# stepperdriver.net
KiCad netlist of a schematic drawn in EAGLE
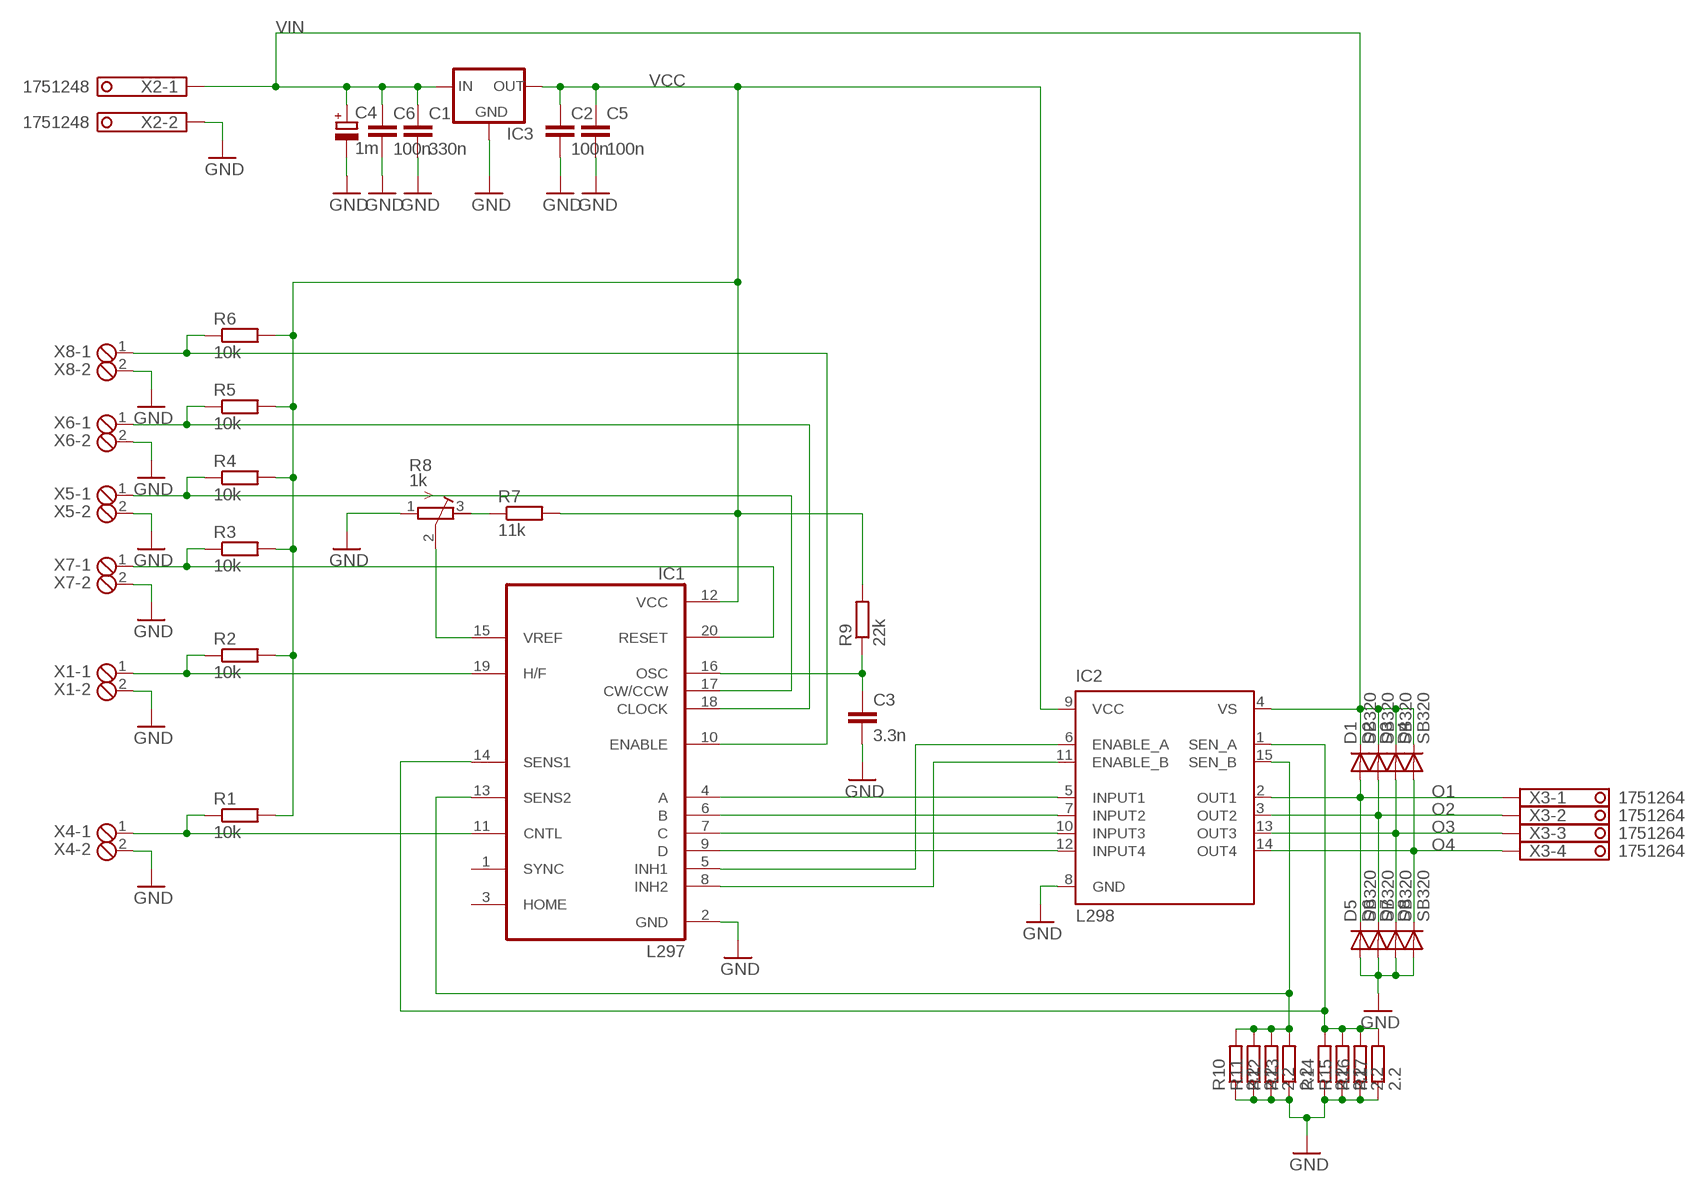
[diagram p0: schematic, sheet 1]

(export (version "E")
  (design (tool "Eeschema 10.0.6"))
  (components
    (comp (ref "C1")
      (value "330n")
      (footprint "eagle-import:C050-035X075")
      (libsource (lib "eagle-import") (part "C-EU050-035X075"))
    )
    (comp (ref "C2")
      (value "100n")
      (footprint "eagle-import:C050-035X075")
      (libsource (lib "eagle-import") (part "C-EU050-035X075"))
    )
    (comp (ref "C3")
      (value "3.3n")
      (footprint "eagle-import:C050-035X075")
      (libsource (lib "eagle-import") (part "C-EU050-035X075"))
    )
    (comp (ref "C4")
      (value "1m")
      (footprint "eagle-import:E5-13")
      (libsource (lib "eagle-import") (part "CPOL-EUE5-13"))
    )
    (comp (ref "C5")
      (value "100n")
      (footprint "eagle-import:C050-035X075")
      (libsource (lib "eagle-import") (part "C-EU050-035X075"))
    )
    (comp (ref "C6")
      (value "100n")
      (footprint "eagle-import:C050-035X075")
      (libsource (lib "eagle-import") (part "C-EU050-035X075"))
    )
    (comp (ref "D1")
      (value "SB320")
      (footprint "eagle-import:DO201-15")
      (libsource (lib "eagle-import") (part "SB320"))
    )
    (comp (ref "D2")
      (value "SB320")
      (footprint "eagle-import:DO201-15")
      (libsource (lib "eagle-import") (part "SB320"))
    )
    (comp (ref "D3")
      (value "SB320")
      (footprint "eagle-import:DO201-15")
      (libsource (lib "eagle-import") (part "SB320"))
    )
    (comp (ref "D4")
      (value "SB320")
      (footprint "eagle-import:DO201-15")
      (libsource (lib "eagle-import") (part "SB320"))
    )
    (comp (ref "D5")
      (value "SB320")
      (footprint "eagle-import:DO201-15")
      (libsource (lib "eagle-import") (part "SB320"))
    )
    (comp (ref "D6")
      (value "SB320")
      (footprint "eagle-import:DO201-15")
      (libsource (lib "eagle-import") (part "SB320"))
    )
    (comp (ref "D7")
      (value "SB320")
      (footprint "eagle-import:DO201-15")
      (libsource (lib "eagle-import") (part "SB320"))
    )
    (comp (ref "D8")
      (value "SB320")
      (footprint "eagle-import:DO201-15")
      (libsource (lib "eagle-import") (part "SB320"))
    )
    (comp (ref "IC1")
      (value "L297")
      (footprint "eagle-import:DIL20")
      (fields (field (name "MPN") "L297/1"))
      (libsource (lib "eagle-import") (part "L297"))
    )
    (comp (ref "IC2")
      (value "L298")
      (footprint "eagle-import:MULTIWATT-15")
      (fields (field (name "MPN") "L298N"))
      (libsource (lib "eagle-import") (part "L298"))
    )
    (comp (ref "IC3")
      (value "78XXS")
      (footprint "eagle-import:78XXS")
      (libsource (lib "eagle-import") (part "78XXS"))
    )
    (comp (ref "R1")
      (value "10k")
      (footprint "eagle-import:0207_10")
      (libsource (lib "eagle-import") (part "R-EU_0207/10"))
    )
    (comp (ref "R2")
      (value "10k")
      (footprint "eagle-import:0207_10")
      (libsource (lib "eagle-import") (part "R-EU_0207/10"))
    )
    (comp (ref "R3")
      (value "10k")
      (footprint "eagle-import:0207_10")
      (libsource (lib "eagle-import") (part "R-EU_0207/10"))
    )
    (comp (ref "R4")
      (value "10k")
      (footprint "eagle-import:0207_10")
      (libsource (lib "eagle-import") (part "R-EU_0207/10"))
    )
    (comp (ref "R5")
      (value "10k")
      (footprint "eagle-import:0207_10")
      (libsource (lib "eagle-import") (part "R-EU_0207/10"))
    )
    (comp (ref "R6")
      (value "10k")
      (footprint "eagle-import:0207_10")
      (libsource (lib "eagle-import") (part "R-EU_0207/10"))
    )
    (comp (ref "R7")
      (value "11k")
      (footprint "eagle-import:0207_10")
      (libsource (lib "eagle-import") (part "R-EU_0207/10"))
    )
    (comp (ref "R8")
      (value "1k")
      (footprint "eagle-import:RTRIM64W")
      (libsource (lib "eagle-import") (part "R-TRIMM64W"))
    )
    (comp (ref "R9")
      (value "22k")
      (footprint "eagle-import:0207_10")
      (libsource (lib "eagle-import") (part "R-EU_0207/10"))
    )
    (comp (ref "R10")
      (value "2.2")
      (footprint "eagle-import:0411_15")
      (libsource (lib "eagle-import") (part "R-EU_0411/15"))
    )
    (comp (ref "R11")
      (value "2.2")
      (footprint "eagle-import:0411_15")
      (libsource (lib "eagle-import") (part "R-EU_0411/15"))
    )
    (comp (ref "R12")
      (value "2.2")
      (footprint "eagle-import:0411_15")
      (libsource (lib "eagle-import") (part "R-EU_0411/15"))
    )
    (comp (ref "R13")
      (value "2.2")
      (footprint "eagle-import:0411_15")
      (libsource (lib "eagle-import") (part "R-EU_0411/15"))
    )
    (comp (ref "R14")
      (value "2.2")
      (footprint "eagle-import:0411_15")
      (libsource (lib "eagle-import") (part "R-EU_0411/15"))
    )
    (comp (ref "R15")
      (value "2.2")
      (footprint "eagle-import:0411_15")
      (libsource (lib "eagle-import") (part "R-EU_0411/15"))
    )
    (comp (ref "R16")
      (value "2.2")
      (footprint "eagle-import:0411_15")
      (libsource (lib "eagle-import") (part "R-EU_0411/15"))
    )
    (comp (ref "R17")
      (value "2.2")
      (footprint "eagle-import:0411_15")
      (libsource (lib "eagle-import") (part "R-EU_0411/15"))
    )
    (comp (ref "X1")
      (value "MPT2")
      (footprint "eagle-import:2POL254")
      (libsource (lib "eagle-import") (part "MPT2"))
    )
    (comp (ref "X2")
      (value "1751248")
      (footprint "eagle-import:1751248")
      (libsource (lib "eagle-import") (part "1751248"))
    )
    (comp (ref "X3")
      (value "1751264")
      (footprint "eagle-import:1751264")
      (libsource (lib "eagle-import") (part "1751264"))
    )
    (comp (ref "X4")
      (value "MPT2")
      (footprint "eagle-import:2POL254")
      (libsource (lib "eagle-import") (part "MPT2"))
    )
    (comp (ref "X5")
      (value "MPT2")
      (footprint "eagle-import:2POL254")
      (libsource (lib "eagle-import") (part "MPT2"))
    )
    (comp (ref "X6")
      (value "MPT2")
      (footprint "eagle-import:2POL254")
      (libsource (lib "eagle-import") (part "MPT2"))
    )
    (comp (ref "X7")
      (value "MPT2")
      (footprint "eagle-import:2POL254")
      (libsource (lib "eagle-import") (part "MPT2"))
    )
    (comp (ref "X8")
      (value "MPT2")
      (footprint "eagle-import:2POL254")
      (libsource (lib "eagle-import") (part "MPT2"))
    )
  )
  (nets
    (net (code "1") (name "/O1") (class "Default")
      (node (ref "D1") (pin "A") (pinfunction "A_A") (pintype "passive"))
      (node (ref "D5") (pin "C") (pinfunction "C_C") (pintype "passive"))
      (node (ref "IC2") (pin "2") (pinfunction "OUT1_2") (pintype "output"))
      (node (ref "X3") (pin "1") (pinfunction "K_1") (pintype "passive"))
    )
    (net (code "2") (name "/O2") (class "Default")
      (node (ref "D2") (pin "A") (pinfunction "A_A") (pintype "passive"))
      (node (ref "D6") (pin "C") (pinfunction "C_C") (pintype "passive"))
      (node (ref "IC2") (pin "3") (pinfunction "OUT2_3") (pintype "output"))
      (node (ref "X3") (pin "2") (pinfunction "K_2") (pintype "passive"))
    )
    (net (code "3") (name "/O3") (class "Default")
      (node (ref "D3") (pin "A") (pinfunction "A_A") (pintype "passive"))
      (node (ref "D7") (pin "C") (pinfunction "C_C") (pintype "passive"))
      (node (ref "IC2") (pin "13") (pinfunction "OUT3_13") (pintype "output"))
      (node (ref "X3") (pin "3") (pinfunction "K_3") (pintype "passive"))
    )
    (net (code "4") (name "/O4") (class "Default")
      (node (ref "D4") (pin "A") (pinfunction "A_A") (pintype "passive"))
      (node (ref "D8") (pin "C") (pinfunction "C_C") (pintype "passive"))
      (node (ref "IC2") (pin "14") (pinfunction "OUT4_14") (pintype "output"))
      (node (ref "X3") (pin "4") (pinfunction "K_4") (pintype "passive"))
    )
    (net (code "5") (name "/VCC") (class "Default")
      (node (ref "C2") (pin "1") (pinfunction "1_1") (pintype "passive"))
      (node (ref "C5") (pin "1") (pinfunction "1_1") (pintype "passive"))
      (node (ref "IC1") (pin "12") (pinfunction "VCC_12") (pintype "power_in"))
      (node (ref "IC2") (pin "9") (pinfunction "VCC_9") (pintype "power_in"))
      (node (ref "IC3") (pin "OUT") (pinfunction "OUT_OUT") (pintype "passive"))
      (node (ref "R1") (pin "2") (pinfunction "2_2") (pintype "passive"))
      (node (ref "R2") (pin "2") (pinfunction "2_2") (pintype "passive"))
      (node (ref "R3") (pin "2") (pinfunction "2_2") (pintype "passive"))
      (node (ref "R4") (pin "2") (pinfunction "2_2") (pintype "passive"))
      (node (ref "R5") (pin "2") (pinfunction "2_2") (pintype "passive"))
      (node (ref "R6") (pin "2") (pinfunction "2_2") (pintype "passive"))
      (node (ref "R7") (pin "2") (pinfunction "2_2") (pintype "passive"))
      (node (ref "R9") (pin "2") (pinfunction "2_2") (pintype "passive"))
    )
    (net (code "6") (name "/VIN") (class "Default")
      (node (ref "C1") (pin "1") (pinfunction "1_1") (pintype "passive"))
      (node (ref "C4") (pin "+") (pinfunction "+_+") (pintype "passive"))
      (node (ref "C6") (pin "1") (pinfunction "1_1") (pintype "passive"))
      (node (ref "D1") (pin "C") (pinfunction "C_C") (pintype "passive"))
      (node (ref "D2") (pin "C") (pinfunction "C_C") (pintype "passive"))
      (node (ref "D3") (pin "C") (pinfunction "C_C") (pintype "passive"))
      (node (ref "D4") (pin "C") (pinfunction "C_C") (pintype "passive"))
      (node (ref "IC2") (pin "4") (pinfunction "VS_4") (pintype "power_in"))
      (node (ref "IC3") (pin "IN") (pinfunction "IN_IN") (pintype "input"))
      (node (ref "X2") (pin "1") (pinfunction "K_1") (pintype "passive"))
    )
    (net (code "7") (name "GND") (class "Default")
      (node (ref "C1") (pin "2") (pinfunction "2_2") (pintype "passive"))
      (node (ref "C2") (pin "2") (pinfunction "2_2") (pintype "passive"))
      (node (ref "C3") (pin "2") (pinfunction "2_2") (pintype "passive"))
      (node (ref "C4") (pin "-") (pinfunction "-_-") (pintype "passive"))
      (node (ref "C5") (pin "2") (pinfunction "2_2") (pintype "passive"))
      (node (ref "C6") (pin "2") (pinfunction "2_2") (pintype "passive"))
      (node (ref "D5") (pin "A") (pinfunction "A_A") (pintype "passive"))
      (node (ref "D6") (pin "A") (pinfunction "A_A") (pintype "passive"))
      (node (ref "D7") (pin "A") (pinfunction "A_A") (pintype "passive"))
      (node (ref "D8") (pin "A") (pinfunction "A_A") (pintype "passive"))
      (node (ref "IC1") (pin "2") (pinfunction "GND_2") (pintype "power_in"))
      (node (ref "IC2") (pin "8") (pinfunction "GND_8") (pintype "power_in"))
      (node (ref "IC3") (pin "GND") (pinfunction "GND_GND") (pintype "input"))
      (node (ref "R10") (pin "1") (pinfunction "1_1") (pintype "passive"))
      (node (ref "R11") (pin "1") (pinfunction "1_1") (pintype "passive"))
      (node (ref "R12") (pin "1") (pinfunction "1_1") (pintype "passive"))
      (node (ref "R13") (pin "1") (pinfunction "1_1") (pintype "passive"))
      (node (ref "R14") (pin "1") (pinfunction "1_1") (pintype "passive"))
      (node (ref "R15") (pin "1") (pinfunction "1_1") (pintype "passive"))
      (node (ref "R16") (pin "1") (pinfunction "1_1") (pintype "passive"))
      (node (ref "R17") (pin "1") (pinfunction "1_1") (pintype "passive"))
      (node (ref "R8") (pin "1") (pinfunction "E_1") (pintype "passive"))
      (node (ref "X1") (pin "2") (pinfunction "1_2") (pintype "passive"))
      (node (ref "X2") (pin "2") (pinfunction "K_2") (pintype "passive"))
      (node (ref "X4") (pin "2") (pinfunction "1_2") (pintype "passive"))
      (node (ref "X5") (pin "2") (pinfunction "1_2") (pintype "passive"))
      (node (ref "X6") (pin "2") (pinfunction "1_2") (pintype "passive"))
      (node (ref "X7") (pin "2") (pinfunction "1_2") (pintype "passive"))
      (node (ref "X8") (pin "2") (pinfunction "1_2") (pintype "passive"))
    )
    (net (code "8") (name "Net-(IC1-A)") (class "Default")
      (node (ref "IC1") (pin "4") (pinfunction "A_4") (pintype "output"))
      (node (ref "IC2") (pin "5") (pinfunction "INPUT1_5") (pintype "input"))
    )
    (net (code "9") (name "Net-(IC1-B)") (class "Default")
      (node (ref "IC1") (pin "6") (pinfunction "B_6") (pintype "output"))
      (node (ref "IC2") (pin "7") (pinfunction "INPUT2_7") (pintype "input"))
    )
    (net (code "10") (name "Net-(IC1-C)") (class "Default")
      (node (ref "IC1") (pin "7") (pinfunction "C_7") (pintype "output"))
      (node (ref "IC2") (pin "10") (pinfunction "INPUT3_10") (pintype "input"))
    )
    (net (code "11") (name "Net-(IC1-CLOCK)") (class "Default")
      (node (ref "IC1") (pin "18") (pinfunction "CLOCK_18") (pintype "input"))
      (node (ref "R5") (pin "1") (pinfunction "1_1") (pintype "passive"))
      (node (ref "X6") (pin "1") (pinfunction "1_1") (pintype "passive"))
    )
    (net (code "12") (name "Net-(IC1-CNTL)") (class "Default")
      (node (ref "IC1") (pin "11") (pinfunction "CNTL_11") (pintype "input"))
      (node (ref "R1") (pin "1") (pinfunction "1_1") (pintype "passive"))
      (node (ref "X4") (pin "1") (pinfunction "1_1") (pintype "passive"))
    )
    (net (code "13") (name "Net-(IC1-CW{slash}CCW)") (class "Default")
      (node (ref "IC1") (pin "17") (pinfunction "CW/CCW_17") (pintype "input"))
      (node (ref "R4") (pin "1") (pinfunction "1_1") (pintype "passive"))
      (node (ref "X5") (pin "1") (pinfunction "1_1") (pintype "passive"))
    )
    (net (code "14") (name "Net-(IC1-D)") (class "Default")
      (node (ref "IC1") (pin "9") (pinfunction "D_9") (pintype "output"))
      (node (ref "IC2") (pin "12") (pinfunction "INPUT4_12") (pintype "input"))
    )
    (net (code "15") (name "Net-(IC1-ENABLE)") (class "Default")
      (node (ref "IC1") (pin "10") (pinfunction "ENABLE_10") (pintype "input"))
      (node (ref "R6") (pin "1") (pinfunction "1_1") (pintype "passive"))
      (node (ref "X8") (pin "1") (pinfunction "1_1") (pintype "passive"))
    )
    (net (code "16") (name "Net-(IC1-H{slash}F)") (class "Default")
      (node (ref "IC1") (pin "19") (pinfunction "H/F_19") (pintype "input"))
      (node (ref "R2") (pin "1") (pinfunction "1_1") (pintype "passive"))
      (node (ref "X1") (pin "1") (pinfunction "1_1") (pintype "passive"))
    )
    (net (code "17") (name "Net-(IC1-INH1)") (class "Default")
      (node (ref "IC1") (pin "5") (pinfunction "INH1_5") (pintype "output"))
      (node (ref "IC2") (pin "6") (pinfunction "ENABLE_A_6") (pintype "input"))
    )
    (net (code "18") (name "Net-(IC1-INH2)") (class "Default")
      (node (ref "IC1") (pin "8") (pinfunction "INH2_8") (pintype "output"))
      (node (ref "IC2") (pin "11") (pinfunction "ENABLE_B_11") (pintype "input"))
    )
    (net (code "19") (name "Net-(IC1-OSC)") (class "Default")
      (node (ref "C3") (pin "1") (pinfunction "1_1") (pintype "passive"))
      (node (ref "IC1") (pin "16") (pinfunction "OSC_16") (pintype "bidirectional"))
      (node (ref "R9") (pin "1") (pinfunction "1_1") (pintype "passive"))
    )
    (net (code "20") (name "Net-(IC1-RESET)") (class "Default")
      (node (ref "IC1") (pin "20") (pinfunction "RESET_20") (pintype "input"))
      (node (ref "R3") (pin "1") (pinfunction "1_1") (pintype "passive"))
      (node (ref "X7") (pin "1") (pinfunction "1_1") (pintype "passive"))
    )
    (net (code "21") (name "Net-(IC1-SENS1)") (class "Default")
      (node (ref "IC1") (pin "14") (pinfunction "SENS1_14") (pintype "output"))
      (node (ref "IC2") (pin "1") (pinfunction "SEN_A_1") (pintype "input"))
      (node (ref "R14") (pin "2") (pinfunction "2_2") (pintype "passive"))
      (node (ref "R15") (pin "2") (pinfunction "2_2") (pintype "passive"))
      (node (ref "R16") (pin "2") (pinfunction "2_2") (pintype "passive"))
      (node (ref "R17") (pin "2") (pinfunction "2_2") (pintype "passive"))
    )
    (net (code "22") (name "Net-(IC1-SENS2)") (class "Default")
      (node (ref "IC1") (pin "13") (pinfunction "SENS2_13") (pintype "output"))
      (node (ref "IC2") (pin "15") (pinfunction "SEN_B_15") (pintype "input"))
      (node (ref "R10") (pin "2") (pinfunction "2_2") (pintype "passive"))
      (node (ref "R11") (pin "2") (pinfunction "2_2") (pintype "passive"))
      (node (ref "R12") (pin "2") (pinfunction "2_2") (pintype "passive"))
      (node (ref "R13") (pin "2") (pinfunction "2_2") (pintype "passive"))
    )
    (net (code "23") (name "Net-(IC1-VREF)") (class "Default")
      (node (ref "IC1") (pin "15") (pinfunction "VREF_15") (pintype "input"))
      (node (ref "R8") (pin "2") (pinfunction "S_2") (pintype "passive"))
    )
    (net (code "24") (name "Net-(R8-A)") (class "Default")
      (node (ref "R7") (pin "1") (pinfunction "1_1") (pintype "passive"))
      (node (ref "R8") (pin "3") (pinfunction "A_3") (pintype "passive"))
    )
    (net (code "25") (name "unconnected-(IC1-HOME-Pad3)") (class "Default")
      (node (ref "IC1") (pin "3") (pinfunction "HOME_3") (pintype "output"))
    )
    (net (code "26") (name "unconnected-(IC1-SYNC-Pad1)") (class "Default")
      (node (ref "IC1") (pin "1") (pinfunction "SYNC_1") (pintype "output"))
    )
  )
)
